# Clock_M-D.net
KiCad netlist of a schematic drawn in EAGLE
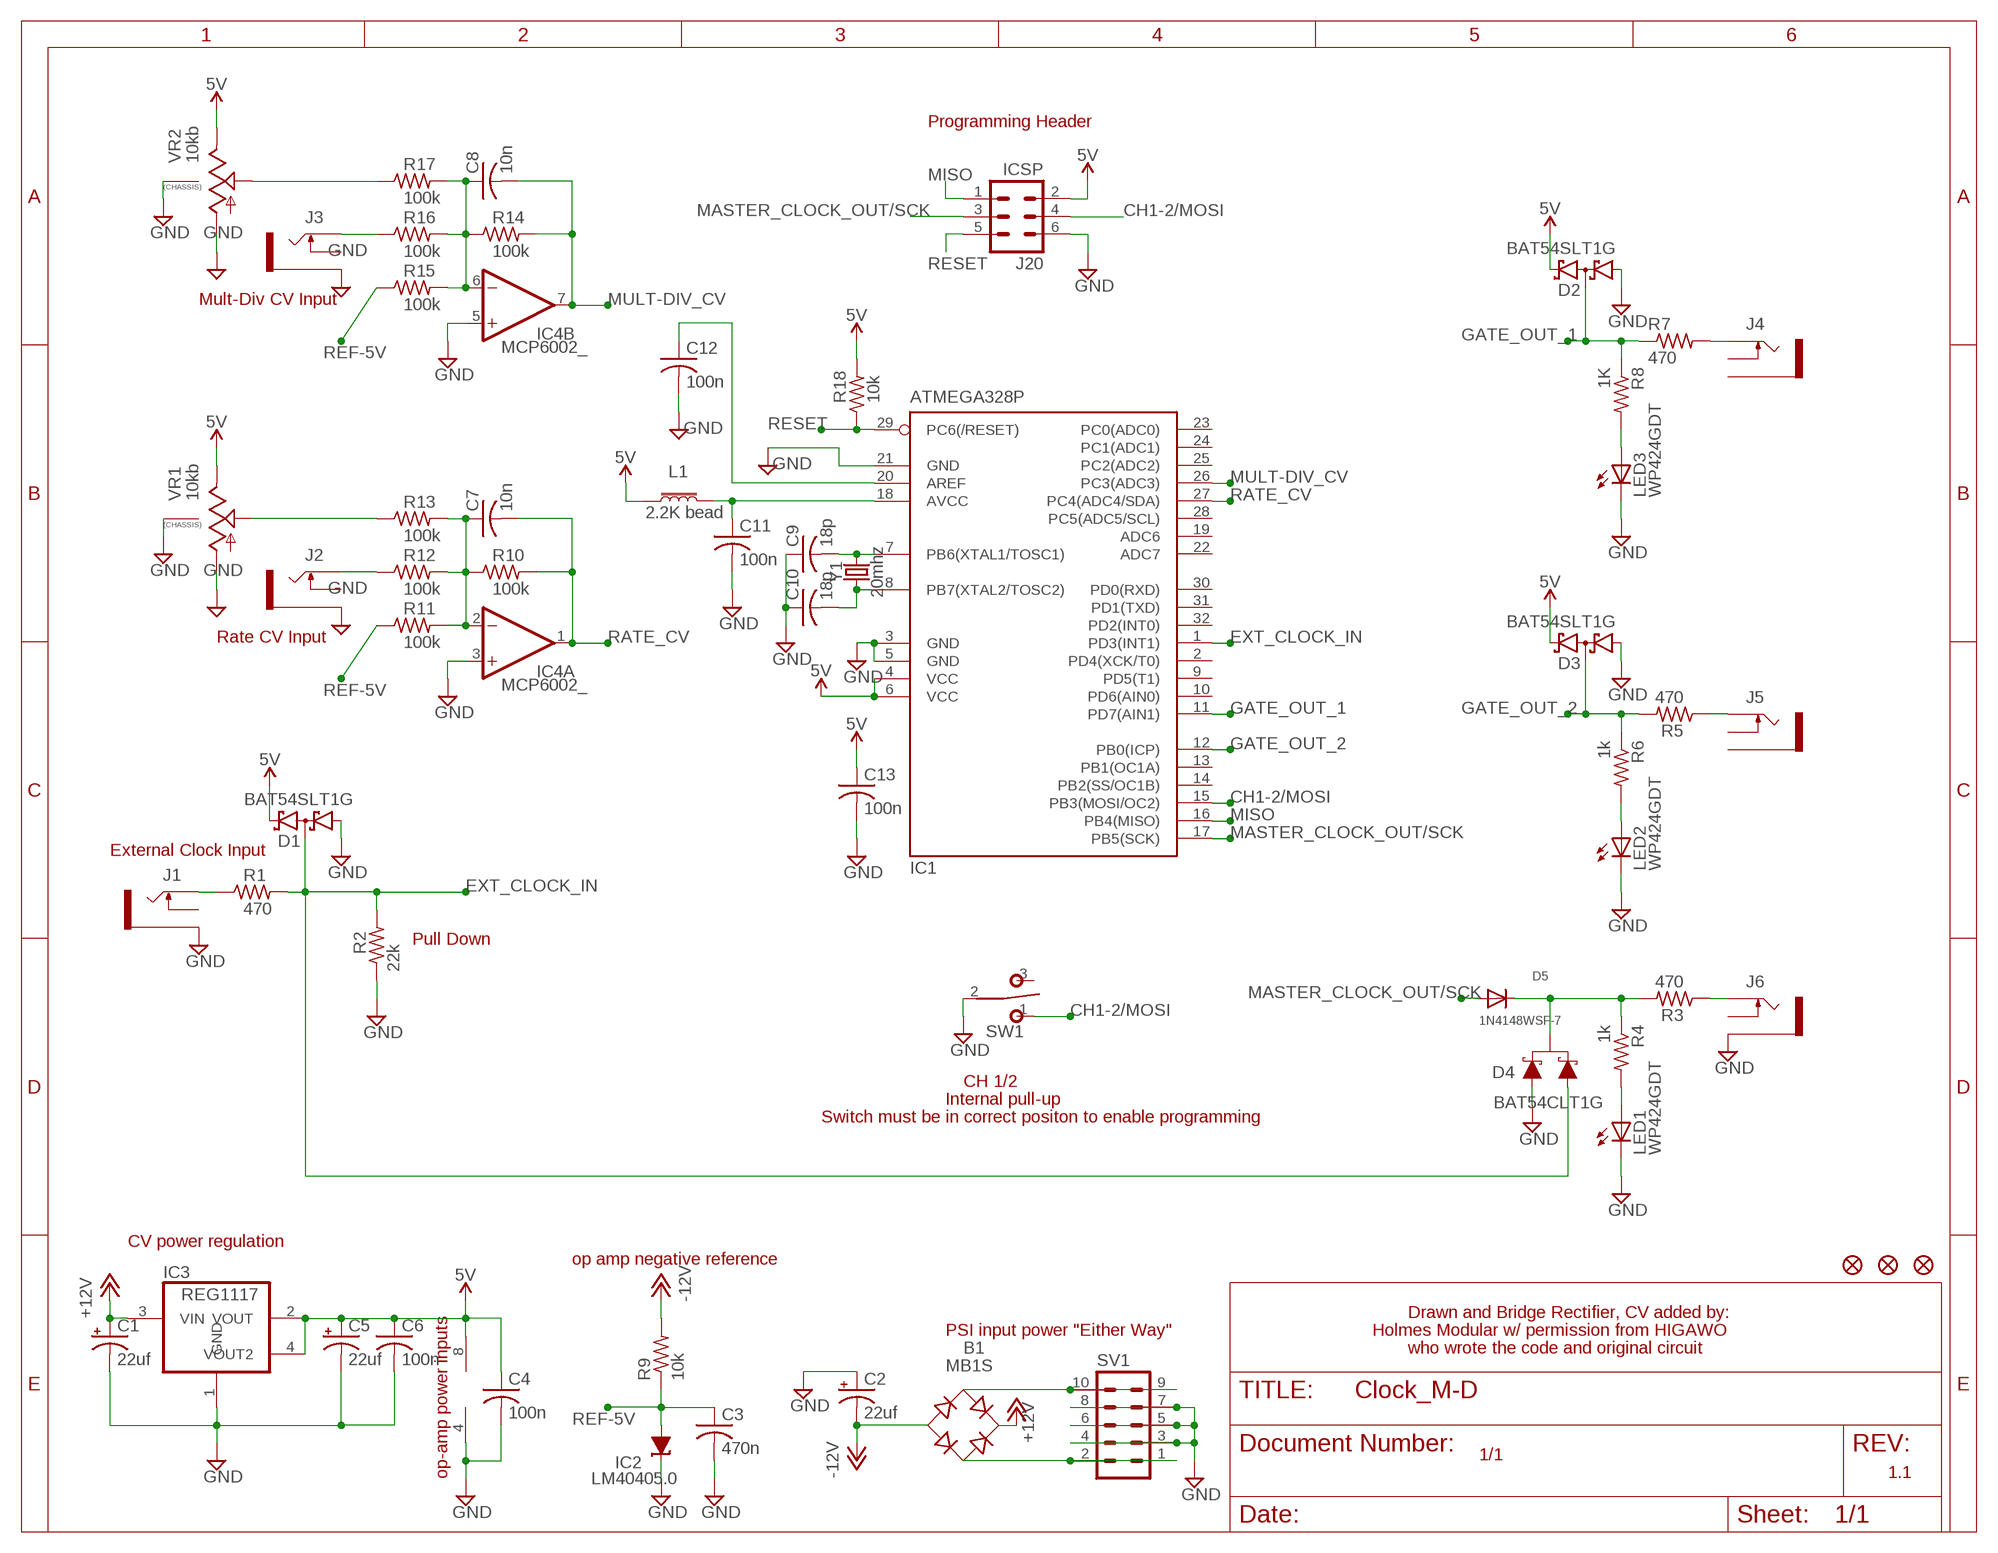
[diagram p0: schematic, sheet 1]

(export (version "E")
  (design (tool "Eeschema 10.0.6"))
  (components
    (comp (ref "B1")
      (value "MB1S")
      (footprint "eagle-import:SOIC-4")
      (libsource (lib "eagle-import") (part "MBS1"))
    )
    (comp (ref "C1")
      (value "22uf")
      (footprint "eagle-import:PANASONIC_C")
      (libsource (lib "eagle-import") (part "CPOL-USC"))
    )
    (comp (ref "C2")
      (value "22uf")
      (footprint "eagle-import:PANASONIC_C")
      (libsource (lib "eagle-import") (part "CPOL-USC"))
    )
    (comp (ref "C3")
      (value "470n")
      (footprint "eagle-import:C0805K")
      (libsource (lib "eagle-import") (part "C-USC0805K"))
    )
    (comp (ref "C4")
      (value "100n")
      (footprint "eagle-import:C0805K")
      (libsource (lib "eagle-import") (part "C-USC0805K"))
    )
    (comp (ref "C5")
      (value "22uf")
      (footprint "eagle-import:PANASONIC_C")
      (libsource (lib "eagle-import") (part "CPOL-USC"))
    )
    (comp (ref "C6")
      (value "100n")
      (footprint "eagle-import:C0805K")
      (libsource (lib "eagle-import") (part "C-USC0805K"))
    )
    (comp (ref "C7")
      (value "10n")
      (footprint "eagle-import:C0805K")
      (libsource (lib "eagle-import") (part "C-USC0805K"))
    )
    (comp (ref "C8")
      (value "10n")
      (footprint "eagle-import:C0805K")
      (libsource (lib "eagle-import") (part "C-USC0805K"))
    )
    (comp (ref "C9")
      (value "18p")
      (footprint "eagle-import:C0805K")
      (libsource (lib "eagle-import") (part "C-USC0805K"))
    )
    (comp (ref "C10")
      (value "18p")
      (footprint "eagle-import:C0805K")
      (libsource (lib "eagle-import") (part "C-USC0805K"))
    )
    (comp (ref "C11")
      (value "100n")
      (footprint "eagle-import:C0805K")
      (libsource (lib "eagle-import") (part "C-USC0805K"))
    )
    (comp (ref "C12")
      (value "100n")
      (footprint "eagle-import:C0805K")
      (libsource (lib "eagle-import") (part "C-USC0805K"))
    )
    (comp (ref "C13")
      (value "100n")
      (footprint "eagle-import:C0805K")
      (libsource (lib "eagle-import") (part "C-USC0805K"))
    )
    (comp (ref "D1")
      (value "BAT54SLT1G")
      (footprint "eagle-import:SOT23")
      (libsource (lib "eagle-import") (part "BAS40-04"))
    )
    (comp (ref "D2")
      (value "BAT54SLT1G")
      (footprint "eagle-import:SOT23")
      (libsource (lib "eagle-import") (part "BAS40-04"))
    )
    (comp (ref "D3")
      (value "BAT54SLT1G")
      (footprint "eagle-import:SOT23")
      (libsource (lib "eagle-import") (part "BAS40-04"))
    )
    (comp (ref "D4")
      (value "BAT54CLT1G")
      (footprint "eagle-import:SOT23-3")
      (libsource (lib "eagle-import") (part "DIODE-SCHOTTKY-DUAL"))
    )
    (comp (ref "D5")
      (value "1N4148WSF-7")
      (footprint "eagle-import:SOD-323F")
      (libsource (lib "eagle-import") (part "DIODESOD-323F"))
    )
    (comp (ref "FD1")
      (value "FIDUCIAL1X2")
      (footprint "eagle-import:FIDUCIAL-1X2")
      (libsource (lib "eagle-import") (part "FIDUCIAL1X2"))
    )
    (comp (ref "FD2")
      (value "FIDUCIAL1X2")
      (footprint "eagle-import:FIDUCIAL-1X2")
      (libsource (lib "eagle-import") (part "FIDUCIAL1X2"))
    )
    (comp (ref "FD3")
      (value "FIDUCIAL1X2")
      (footprint "eagle-import:FIDUCIAL-1X2")
      (libsource (lib "eagle-import") (part "FIDUCIAL1X2"))
    )
    (comp (ref "IC1")
      (value "ATMEGA328P")
      (footprint "eagle-import:TQFP32-08")
      (fields (field (name "MPN") "ATMEGA8-16AU"))
      (libsource (lib "eagle-import") (part "MEGA8-AI"))
    )
    (comp (ref "IC2")
      (value "LM40405.0")
      (footprint "eagle-import:DBZ_R-PDSO-G3")
      (fields (field (name "MPN") "LM4041A12IDBZR"))
      (libsource (lib "eagle-import") (part "LM4041DBZA12"))
    )
    (comp (ref "IC3")
      (value "REG1117")
      (footprint "eagle-import:SOT223")
      (libsource (lib "eagle-import") (part "REG1117"))
    )
    (comp (ref "IC4")
      (value "MCP6002_")
      (footprint "eagle-import:SO08")
      (libsource (lib "eagle-import") (part "MCP6002_"))
    )
    (comp (ref "J1")
      (value "THONKICONNNEW")
      (footprint "eagle-import:WQP-PJ301M-12_JACK")
      (libsource (lib "eagle-import") (part "THONKICONNNEW"))
    )
    (comp (ref "J2")
      (value "THONKICONNNEW")
      (footprint "eagle-import:WQP-PJ301M-12_JACK")
      (libsource (lib "eagle-import") (part "THONKICONNNEW"))
    )
    (comp (ref "J3")
      (value "THONKICONNNEW")
      (footprint "eagle-import:WQP-PJ301M-12_JACK")
      (libsource (lib "eagle-import") (part "THONKICONNNEW"))
    )
    (comp (ref "J4")
      (value "THONKICONNNEW")
      (footprint "eagle-import:WQP-PJ301M-12_JACK")
      (libsource (lib "eagle-import") (part "THONKICONNNEW"))
    )
    (comp (ref "J5")
      (value "THONKICONNNEW")
      (footprint "eagle-import:WQP-PJ301M-12_JACK")
      (libsource (lib "eagle-import") (part "THONKICONNNEW"))
    )
    (comp (ref "J6")
      (value "THONKICONNNEW")
      (footprint "eagle-import:WQP-PJ301M-12_JACK")
      (libsource (lib "eagle-import") (part "THONKICONNNEW"))
    )
    (comp (ref "J20")
      (value "ICSP")
      (footprint "eagle-import:MA03-2")
      (libsource (lib "eagle-import") (part "MA03-2"))
    )
    (comp (ref "L1")
      (value "2.2K bead")
      (footprint "eagle-import:0603")
      (libsource (lib "eagle-import") (part "FERRITE_BEAD-0603"))
    )
    (comp (ref "LED1")
      (value "WP424GDT")
      (footprint "eagle-import:LED3MM")
      (libsource (lib "eagle-import") (part "LED3MM"))
    )
    (comp (ref "LED2")
      (value "WP424GDT")
      (footprint "eagle-import:LED3MM")
      (libsource (lib "eagle-import") (part "LED3MM"))
    )
    (comp (ref "LED3")
      (value "WP424GDT")
      (footprint "eagle-import:LED3MM")
      (libsource (lib "eagle-import") (part "LED3MM"))
    )
    (comp (ref "R1")
      (value "470")
      (footprint "eagle-import:R0805")
      (libsource (lib "eagle-import") (part "R-US_R0805"))
    )
    (comp (ref "R2")
      (value "22k")
      (footprint "eagle-import:R0805")
      (libsource (lib "eagle-import") (part "R-US_R0805"))
    )
    (comp (ref "R3")
      (value "470")
      (footprint "eagle-import:R0805")
      (libsource (lib "eagle-import") (part "R-US_R0805"))
    )
    (comp (ref "R4")
      (value "1k")
      (footprint "eagle-import:R0805")
      (libsource (lib "eagle-import") (part "R-US_R0805"))
    )
    (comp (ref "R5")
      (value "470")
      (footprint "eagle-import:R0805")
      (libsource (lib "eagle-import") (part "R-US_R0805"))
    )
    (comp (ref "R6")
      (value "1k")
      (footprint "eagle-import:R0805")
      (libsource (lib "eagle-import") (part "R-US_R0805"))
    )
    (comp (ref "R7")
      (value "470")
      (footprint "eagle-import:R0805")
      (libsource (lib "eagle-import") (part "R-US_R0805"))
    )
    (comp (ref "R8")
      (value "1K")
      (footprint "eagle-import:R0805")
      (libsource (lib "eagle-import") (part "R-US_R0805"))
    )
    (comp (ref "R9")
      (value "10k")
      (footprint "eagle-import:R0805")
      (libsource (lib "eagle-import") (part "R-US_R0805"))
    )
    (comp (ref "R10")
      (value "100k")
      (footprint "eagle-import:R0805")
      (libsource (lib "eagle-import") (part "R-US_R0805"))
    )
    (comp (ref "R11")
      (value "100k")
      (footprint "eagle-import:R0805")
      (libsource (lib "eagle-import") (part "R-US_R0805"))
    )
    (comp (ref "R12")
      (value "100k")
      (footprint "eagle-import:R0805")
      (libsource (lib "eagle-import") (part "R-US_R0805"))
    )
    (comp (ref "R13")
      (value "100k")
      (footprint "eagle-import:R0805")
      (libsource (lib "eagle-import") (part "R-US_R0805"))
    )
    (comp (ref "R14")
      (value "100k")
      (footprint "eagle-import:R0805")
      (libsource (lib "eagle-import") (part "R-US_R0805"))
    )
    (comp (ref "R15")
      (value "100k")
      (footprint "eagle-import:R0805")
      (libsource (lib "eagle-import") (part "R-US_R0805"))
    )
    (comp (ref "R16")
      (value "100k")
      (footprint "eagle-import:R0805")
      (libsource (lib "eagle-import") (part "R-US_R0805"))
    )
    (comp (ref "R17")
      (value "100k")
      (footprint "eagle-import:R0805")
      (libsource (lib "eagle-import") (part "R-US_R0805"))
    )
    (comp (ref "R18")
      (value "10k")
      (footprint "eagle-import:R0805")
      (libsource (lib "eagle-import") (part "R-US_R0805"))
    )
    (comp (ref "SV1")
      (value "EURO_POWER_HEADERLOCK")
      (footprint "eagle-import:10PIN_BACKSIDE")
      (libsource (lib "eagle-import") (part "10PIN_BACKSIDE"))
    )
    (comp (ref "SW1")
      (value "T-80-T-SPDT-ON-OFF-ON")
      (footprint "eagle-import:M9040P")
      (libsource (lib "eagle-import") (part "T-80-T-SPDT-ON-OFF-ON"))
    )
    (comp (ref "VR1")
      (value "10kb")
      (footprint "eagle-import:9MM_SNAP-IN_POT")
      (libsource (lib "eagle-import") (part "9MM_SNAP-IN_POT_CHASSIS"))
    )
    (comp (ref "VR2")
      (value "10kb")
      (footprint "eagle-import:9MM_SNAP-IN_POT")
      (libsource (lib "eagle-import") (part "9MM_SNAP-IN_POT_CHASSIS"))
    )
    (comp (ref "Y1")
      (value "20mhz")
      (footprint "eagle-import:CRYSTAL-SMD-5X3.2-2PAD")
      (libsource (lib "eagle-import") (part "CRYSTALSMD-5X3.2-2PAD"))
    )
  )
  (nets
    (net (code "1") (name "+12V") (class "Default")
      (node (ref "B1") (pin "+") (pinfunction "+_+") (pintype "passive"))
      (node (ref "C1") (pin "+") (pinfunction "+_+") (pintype "passive"))
      (node (ref "IC3") (pin "3") (pinfunction "VIN_3") (pintype "input"))
    )
    (net (code "2") (name "-12V") (class "Default")
      (node (ref "B1") (pin "-") (pinfunction "-_-") (pintype "passive"))
      (node (ref "C2") (pin "-") (pinfunction "-_-") (pintype "passive"))
      (node (ref "R9") (pin "2") (pinfunction "2_2") (pintype "passive"))
    )
    (net (code "3") (name "/CH1-2{slash}MOSI") (class "Default")
      (node (ref "IC1") (pin "15") (pinfunction "PB3(MOSI/OC2)_15") (pintype "bidirectional"))
      (node (ref "J20") (pin "4") (pinfunction "4_4") (pintype "passive"))
      (node (ref "SW1") (pin "1") (pinfunction "O_1") (pintype "passive"))
    )
    (net (code "4") (name "/EXT_CLOCK_IN") (class "Default")
      (node (ref "D1") (pin "3") (pinfunction "C1A2_3") (pintype "passive"))
      (node (ref "D4") (pin "2") (pinfunction "A1_2") (pintype "passive"))
      (node (ref "IC1") (pin "1") (pinfunction "PD3(INT1)_1") (pintype "bidirectional"))
      (node (ref "R1") (pin "2") (pinfunction "2_2") (pintype "passive"))
      (node (ref "R2") (pin "2") (pinfunction "2_2") (pintype "passive"))
    )
    (net (code "5") (name "/GATE_OUT_1") (class "Default")
      (node (ref "D2") (pin "3") (pinfunction "C1A2_3") (pintype "passive"))
      (node (ref "IC1") (pin "11") (pinfunction "PD7(AIN1)_11") (pintype "bidirectional"))
      (node (ref "R7") (pin "1") (pinfunction "1_1") (pintype "passive"))
      (node (ref "R8") (pin "1") (pinfunction "1_1") (pintype "passive"))
    )
    (net (code "6") (name "/GATE_OUT_2") (class "Default")
      (node (ref "D3") (pin "3") (pinfunction "C1A2_3") (pintype "passive"))
      (node (ref "IC1") (pin "12") (pinfunction "PB0(ICP)_12") (pintype "bidirectional"))
      (node (ref "R5") (pin "2") (pinfunction "2_2") (pintype "passive"))
      (node (ref "R6") (pin "1") (pinfunction "1_1") (pintype "passive"))
    )
    (net (code "7") (name "/MASTER_CLOCK_OUT{slash}SCK") (class "Default")
      (node (ref "D5") (pin "A") (pinfunction "A_A") (pintype "passive"))
      (node (ref "IC1") (pin "17") (pinfunction "PB5(SCK)_17") (pintype "bidirectional"))
      (node (ref "J20") (pin "3") (pinfunction "3_3") (pintype "passive"))
    )
    (net (code "8") (name "/MISO") (class "Default")
      (node (ref "IC1") (pin "16") (pinfunction "PB4(MISO)_16") (pintype "bidirectional"))
      (node (ref "J20") (pin "1") (pinfunction "1_1") (pintype "passive"))
    )
    (net (code "9") (name "/MULT-DIV_CV") (class "Default")
      (node (ref "C8") (pin "2") (pinfunction "2_2") (pintype "passive"))
      (node (ref "IC1") (pin "26") (pinfunction "PC3(ADC3)_26") (pintype "bidirectional"))
      (node (ref "IC4") (pin "7") (pinfunction "OUT_7") (pintype "output"))
      (node (ref "R14") (pin "2") (pinfunction "2_2") (pintype "passive"))
    )
    (net (code "10") (name "/RATE_CV") (class "Default")
      (node (ref "C7") (pin "2") (pinfunction "2_2") (pintype "passive"))
      (node (ref "IC1") (pin "27") (pinfunction "PC4(ADC4/SDA)_27") (pintype "bidirectional"))
      (node (ref "IC4") (pin "1") (pinfunction "OUT_1") (pintype "output"))
      (node (ref "R10") (pin "2") (pinfunction "2_2") (pintype "passive"))
    )
    (net (code "11") (name "/REF-5V") (class "Default")
      (node (ref "C3") (pin "1") (pinfunction "1_1") (pintype "passive"))
      (node (ref "IC2") (pin "2") (pinfunction "A_2") (pintype "passive"))
      (node (ref "R11") (pin "1") (pinfunction "1_1") (pintype "passive"))
      (node (ref "R15") (pin "1") (pinfunction "1_1") (pintype "passive"))
      (node (ref "R9") (pin "1") (pinfunction "1_1") (pintype "passive"))
    )
    (net (code "12") (name "/RESET") (class "Default")
      (node (ref "IC1") (pin "29") (pinfunction "PC6(/RESET)_29") (pintype "bidirectional"))
      (node (ref "J20") (pin "5") (pinfunction "5_5") (pintype "passive"))
      (node (ref "R18") (pin "1") (pinfunction "1_1") (pintype "passive"))
    )
    (net (code "13") (name "5V") (class "Default")
      (node (ref "C13") (pin "1") (pinfunction "1_1") (pintype "passive"))
      (node (ref "C4") (pin "1") (pinfunction "1_1") (pintype "passive"))
      (node (ref "C5") (pin "+") (pinfunction "+_+") (pintype "passive"))
      (node (ref "C6") (pin "1") (pinfunction "1_1") (pintype "passive"))
      (node (ref "D1") (pin "2") (pinfunction "C2_2") (pintype "passive"))
      (node (ref "D2") (pin "2") (pinfunction "C2_2") (pintype "passive"))
      (node (ref "D3") (pin "2") (pinfunction "C2_2") (pintype "passive"))
      (node (ref "IC1") (pin "4") (pinfunction "VCC_4") (pintype "power_in"))
      (node (ref "IC1") (pin "6") (pinfunction "VCC_6") (pintype "power_in"))
      (node (ref "IC3") (pin "2") (pinfunction "VOUT_2") (pintype "output"))
      (node (ref "IC3") (pin "4") (pinfunction "VOUT2_4") (pintype "output"))
      (node (ref "IC4") (pin "8") (pinfunction "V+_8") (pintype "power_in"))
      (node (ref "J20") (pin "2") (pinfunction "2_2") (pintype "passive"))
      (node (ref "L1") (pin "1") (pinfunction "1_1") (pintype "passive"))
      (node (ref "R18") (pin "2") (pinfunction "2_2") (pintype "passive"))
      (node (ref "VR1") (pin "3") (pinfunction "E_3") (pintype "passive"))
      (node (ref "VR2") (pin "3") (pinfunction "E_3") (pintype "passive"))
    )
    (net (code "14") (name "GND") (class "Default")
      (node (ref "C1") (pin "-") (pinfunction "-_-") (pintype "passive"))
      (node (ref "C10") (pin "1") (pinfunction "1_1") (pintype "passive"))
      (node (ref "C11") (pin "2") (pinfunction "2_2") (pintype "passive"))
      (node (ref "C12") (pin "2") (pinfunction "2_2") (pintype "passive"))
      (node (ref "C13") (pin "2") (pinfunction "2_2") (pintype "passive"))
      (node (ref "C2") (pin "+") (pinfunction "+_+") (pintype "passive"))
      (node (ref "C3") (pin "2") (pinfunction "2_2") (pintype "passive"))
      (node (ref "C4") (pin "2") (pinfunction "2_2") (pintype "passive"))
      (node (ref "C5") (pin "-") (pinfunction "-_-") (pintype "passive"))
      (node (ref "C6") (pin "2") (pinfunction "2_2") (pintype "passive"))
      (node (ref "C9") (pin "1") (pinfunction "1_1") (pintype "passive"))
      (node (ref "D1") (pin "1") (pinfunction "A1_1") (pintype "passive"))
      (node (ref "D2") (pin "1") (pinfunction "A1_1") (pintype "passive"))
      (node (ref "D3") (pin "1") (pinfunction "A1_1") (pintype "passive"))
      (node (ref "D4") (pin "1") (pinfunction "A_1") (pintype "passive"))
      (node (ref "IC1") (pin "21") (pinfunction "GND_21") (pintype "power_in"))
      (node (ref "IC1") (pin "3") (pinfunction "GND_3") (pintype "power_in"))
      (node (ref "IC1") (pin "5") (pinfunction "GND_5") (pintype "power_in"))
      (node (ref "IC2") (pin "1") (pinfunction "C_1") (pintype "passive"))
      (node (ref "IC3") (pin "1") (pinfunction "GND_1") (pintype "power_in"))
      (node (ref "IC4") (pin "3") (pinfunction "+IN_3") (pintype "input"))
      (node (ref "IC4") (pin "4") (pinfunction "V-_4") (pintype "power_in"))
      (node (ref "IC4") (pin "5") (pinfunction "+IN_5") (pintype "input"))
      (node (ref "J1") (pin "P$3_SLEEVE") (pinfunction "SLEEVE_P$3_SLEEVE") (pintype "passive"))
      (node (ref "J2") (pin "P$3_SLEEVE") (pinfunction "SLEEVE_P$3_SLEEVE") (pintype "passive"))
      (node (ref "J20") (pin "6") (pinfunction "6_6") (pintype "passive"))
      (node (ref "J3") (pin "P$3_SLEEVE") (pinfunction "SLEEVE_P$3_SLEEVE") (pintype "passive"))
      (node (ref "J6") (pin "P$3_SLEEVE") (pinfunction "SLEEVE_P$3_SLEEVE") (pintype "passive"))
      (node (ref "LED1") (pin "K") (pinfunction "C_K") (pintype "passive"))
      (node (ref "LED2") (pin "K") (pinfunction "C_K") (pintype "passive"))
      (node (ref "LED3") (pin "K") (pinfunction "C_K") (pintype "passive"))
      (node (ref "R2") (pin "1") (pinfunction "1_1") (pintype "passive"))
      (node (ref "SV1") (pin "3") (pinfunction "3_3") (pintype "passive"))
      (node (ref "SV1") (pin "4") (pinfunction "4_4") (pintype "passive"))
      (node (ref "SV1") (pin "5") (pinfunction "5_5") (pintype "passive"))
      (node (ref "SV1") (pin "6") (pinfunction "6_6") (pintype "passive"))
      (node (ref "SV1") (pin "7") (pinfunction "7_7") (pintype "passive"))
      (node (ref "SV1") (pin "8") (pinfunction "8_8") (pintype "passive"))
      (node (ref "SW1") (pin "2") (pinfunction "P_2") (pintype "passive"))
      (node (ref "VR1") (pin "1") (pinfunction "A_1") (pintype "passive"))
      (node (ref "VR1") (pin "CHASSIS1") (pinfunction "P$1_CHASSIS1") (pintype "passive"))
      (node (ref "VR1") (pin "CHASSIS2") (pinfunction "P$1_CHASSIS2") (pintype "passive"))
      (node (ref "VR2") (pin "1") (pinfunction "A_1") (pintype "passive"))
      (node (ref "VR2") (pin "CHASSIS1") (pinfunction "P$1_CHASSIS1") (pintype "passive"))
      (node (ref "VR2") (pin "CHASSIS2") (pinfunction "P$1_CHASSIS2") (pintype "passive"))
    )
    (net (code "15") (name "Net-(B1-AC1)") (class "Default")
      (node (ref "B1") (pin "~1") (pinfunction "AC1_~1") (pintype "passive"))
      (node (ref "SV1") (pin "10") (pinfunction "10_10") (pintype "passive"))
      (node (ref "SV1") (pin "9") (pinfunction "9_9") (pintype "passive"))
    )
    (net (code "16") (name "Net-(B1-AC2)") (class "Default")
      (node (ref "B1") (pin "~2") (pinfunction "AC2_~2") (pintype "passive"))
      (node (ref "SV1") (pin "1") (pinfunction "1_1") (pintype "passive"))
      (node (ref "SV1") (pin "2") (pinfunction "2_2") (pintype "passive"))
    )
    (net (code "17") (name "Net-(D4-C)") (class "Default")
      (node (ref "D4") (pin "3") (pinfunction "C_3") (pintype "passive"))
      (node (ref "D5") (pin "C") (pinfunction "C_C") (pintype "passive"))
      (node (ref "R3") (pin "2") (pinfunction "2_2") (pintype "passive"))
      (node (ref "R4") (pin "1") (pinfunction "1_1") (pintype "passive"))
    )
    (net (code "18") (name "Net-(IC1-AREF)") (class "Default")
      (node (ref "C12") (pin "1") (pinfunction "1_1") (pintype "passive"))
      (node (ref "IC1") (pin "20") (pinfunction "AREF_20") (pintype "passive"))
    )
    (net (code "19") (name "Net-(IC1-AVCC)") (class "Default")
      (node (ref "C11") (pin "1") (pinfunction "1_1") (pintype "passive"))
      (node (ref "IC1") (pin "18") (pinfunction "AVCC_18") (pintype "power_in"))
      (node (ref "L1") (pin "2") (pinfunction "2_2") (pintype "passive"))
    )
    (net (code "20") (name "Net-(IC1-PB6(XTAL1{slash}TOSC1))") (class "Default")
      (node (ref "C9") (pin "2") (pinfunction "2_2") (pintype "passive"))
      (node (ref "IC1") (pin "7") (pinfunction "PB6(XTAL1/TOSC1)_7") (pintype "bidirectional"))
      (node (ref "Y1") (pin "P$2") (pinfunction "2_P$2") (pintype "passive"))
    )
    (net (code "21") (name "Net-(IC1-PB7(XTAL2{slash}TOSC2))") (class "Default")
      (node (ref "C10") (pin "2") (pinfunction "2_2") (pintype "passive"))
      (node (ref "IC1") (pin "8") (pinfunction "PB7(XTAL2/TOSC2)_8") (pintype "bidirectional"))
      (node (ref "Y1") (pin "P$1") (pinfunction "1_P$1") (pintype "passive"))
    )
    (net (code "22") (name "Net-(IC4A--IN)") (class "Default")
      (node (ref "C7") (pin "1") (pinfunction "1_1") (pintype "passive"))
      (node (ref "IC4") (pin "2") (pinfunction "-IN_2") (pintype "input"))
      (node (ref "R10") (pin "1") (pinfunction "1_1") (pintype "passive"))
      (node (ref "R11") (pin "2") (pinfunction "2_2") (pintype "passive"))
      (node (ref "R12") (pin "2") (pinfunction "2_2") (pintype "passive"))
      (node (ref "R13") (pin "2") (pinfunction "2_2") (pintype "passive"))
    )
    (net (code "23") (name "Net-(IC4B--IN)") (class "Default")
      (node (ref "C8") (pin "1") (pinfunction "1_1") (pintype "passive"))
      (node (ref "IC4") (pin "6") (pinfunction "-IN_6") (pintype "input"))
      (node (ref "R14") (pin "1") (pinfunction "1_1") (pintype "passive"))
      (node (ref "R15") (pin "2") (pinfunction "2_2") (pintype "passive"))
      (node (ref "R16") (pin "2") (pinfunction "2_2") (pintype "passive"))
      (node (ref "R17") (pin "2") (pinfunction "2_2") (pintype "passive"))
    )
    (net (code "24") (name "Net-(J1-TIP)") (class "Default")
      (node (ref "J1") (pin "P$1_TIP") (pinfunction "TIP_P$1_TIP") (pintype "passive"))
      (node (ref "R1") (pin "1") (pinfunction "1_1") (pintype "passive"))
    )
    (net (code "25") (name "Net-(J2-TIP)") (class "Default")
      (node (ref "J2") (pin "P$1_TIP") (pinfunction "TIP_P$1_TIP") (pintype "passive"))
      (node (ref "R12") (pin "1") (pinfunction "1_1") (pintype "passive"))
    )
    (net (code "26") (name "Net-(J3-TIP)") (class "Default")
      (node (ref "J3") (pin "P$1_TIP") (pinfunction "TIP_P$1_TIP") (pintype "passive"))
      (node (ref "R16") (pin "1") (pinfunction "1_1") (pintype "passive"))
    )
    (net (code "27") (name "Net-(J4-TIP)") (class "Default")
      (node (ref "J4") (pin "P$1_TIP") (pinfunction "TIP_P$1_TIP") (pintype "passive"))
      (node (ref "R7") (pin "2") (pinfunction "2_2") (pintype "passive"))
    )
    (net (code "28") (name "Net-(J5-TIP)") (class "Default")
      (node (ref "J5") (pin "P$1_TIP") (pinfunction "TIP_P$1_TIP") (pintype "passive"))
      (node (ref "R5") (pin "1") (pinfunction "1_1") (pintype "passive"))
    )
    (net (code "29") (name "Net-(J6-TIP)") (class "Default")
      (node (ref "J6") (pin "P$1_TIP") (pinfunction "TIP_P$1_TIP") (pintype "passive"))
      (node (ref "R3") (pin "1") (pinfunction "1_1") (pintype "passive"))
    )
    (net (code "30") (name "Net-(LED1-PadA)") (class "Default")
      (node (ref "LED1") (pin "A") (pinfunction "A_A") (pintype "passive"))
      (node (ref "R4") (pin "2") (pinfunction "2_2") (pintype "passive"))
    )
    (net (code "31") (name "Net-(LED2-PadA)") (class "Default")
      (node (ref "LED2") (pin "A") (pinfunction "A_A") (pintype "passive"))
      (node (ref "R6") (pin "2") (pinfunction "2_2") (pintype "passive"))
    )
    (net (code "32") (name "Net-(LED3-PadA)") (class "Default")
      (node (ref "LED3") (pin "A") (pinfunction "A_A") (pintype "passive"))
      (node (ref "R8") (pin "2") (pinfunction "2_2") (pintype "passive"))
    )
    (net (code "33") (name "Net-(VR1-S)") (class "Default")
      (node (ref "R13") (pin "1") (pinfunction "1_1") (pintype "passive"))
      (node (ref "VR1") (pin "2") (pinfunction "S_2") (pintype "passive"))
    )
    (net (code "34") (name "Net-(VR2-S)") (class "Default")
      (node (ref "R17") (pin "1") (pinfunction "1_1") (pintype "passive"))
      (node (ref "VR2") (pin "2") (pinfunction "S_2") (pintype "passive"))
    )
    (net (code "35") (name "unconnected-(IC1-ADC6-Pad19)") (class "Default")
      (node (ref "IC1") (pin "19") (pinfunction "ADC6_19") (pintype "bidirectional"))
    )
    (net (code "36") (name "unconnected-(IC1-ADC7-Pad22)") (class "Default")
      (node (ref "IC1") (pin "22") (pinfunction "ADC7_22") (pintype "bidirectional"))
    )
    (net (code "37") (name "unconnected-(IC1-PB1(OC1A)-Pad13)") (class "Default")
      (node (ref "IC1") (pin "13") (pinfunction "PB1(OC1A)_13") (pintype "bidirectional"))
    )
    (net (code "38") (name "unconnected-(IC1-PB2(SS{slash}OC1B)-Pad14)") (class "Default")
      (node (ref "IC1") (pin "14") (pinfunction "PB2(SS/OC1B)_14") (pintype "bidirectional"))
    )
    (net (code "39") (name "unconnected-(IC1-PC0(ADC0)-Pad23)") (class "Default")
      (node (ref "IC1") (pin "23") (pinfunction "PC0(ADC0)_23") (pintype "bidirectional"))
    )
    (net (code "40") (name "unconnected-(IC1-PC1(ADC1)-Pad24)") (class "Default")
      (node (ref "IC1") (pin "24") (pinfunction "PC1(ADC1)_24") (pintype "bidirectional"))
    )
    (net (code "41") (name "unconnected-(IC1-PC2(ADC2)-Pad25)") (class "Default")
      (node (ref "IC1") (pin "25") (pinfunction "PC2(ADC2)_25") (pintype "bidirectional"))
    )
    (net (code "42") (name "unconnected-(IC1-PC5(ADC5{slash}SCL)-Pad28)") (class "Default")
      (node (ref "IC1") (pin "28") (pinfunction "PC5(ADC5/SCL)_28") (pintype "bidirectional"))
    )
    (net (code "43") (name "unconnected-(IC1-PD0(RXD)-Pad30)") (class "Default")
      (node (ref "IC1") (pin "30") (pinfunction "PD0(RXD)_30") (pintype "bidirectional"))
    )
    (net (code "44") (name "unconnected-(IC1-PD1(TXD)-Pad31)") (class "Default")
      (node (ref "IC1") (pin "31") (pinfunction "PD1(TXD)_31") (pintype "bidirectional"))
    )
    (net (code "45") (name "unconnected-(IC1-PD2(INT0)-Pad32)") (class "Default")
      (node (ref "IC1") (pin "32") (pinfunction "PD2(INT0)_32") (pintype "bidirectional"))
    )
    (net (code "46") (name "unconnected-(IC1-PD4(XCK{slash}T0)-Pad2)") (class "Default")
      (node (ref "IC1") (pin "2") (pinfunction "PD4(XCK/T0)_2") (pintype "bidirectional"))
    )
    (net (code "47") (name "unconnected-(IC1-PD5(T1)-Pad9)") (class "Default")
      (node (ref "IC1") (pin "9") (pinfunction "PD5(T1)_9") (pintype "bidirectional"))
    )
    (net (code "48") (name "unconnected-(IC1-PD6(AIN0)-Pad10)") (class "Default")
      (node (ref "IC1") (pin "10") (pinfunction "PD6(AIN0)_10") (pintype "bidirectional"))
    )
    (net (code "49") (name "unconnected-(J1-SWITCH-PadP$2_SWITCH)") (class "Default")
      (node (ref "J1") (pin "P$2_SWITCH") (pinfunction "SWITCH_P$2_SWITCH") (pintype "passive"))
    )
    (net (code "50") (name "unconnected-(J2-SWITCH-PadP$2_SWITCH)") (class "Default")
      (node (ref "J2") (pin "P$2_SWITCH") (pinfunction "SWITCH_P$2_SWITCH") (pintype "passive"))
    )
    (net (code "51") (name "unconnected-(J3-SWITCH-PadP$2_SWITCH)") (class "Default")
      (node (ref "J3") (pin "P$2_SWITCH") (pinfunction "SWITCH_P$2_SWITCH") (pintype "passive"))
    )
    (net (code "52") (name "unconnected-(J4-SLEEVE-PadP$3_SLEEVE)") (class "Default")
      (node (ref "J4") (pin "P$3_SLEEVE") (pinfunction "SLEEVE_P$3_SLEEVE") (pintype "passive"))
    )
    (net (code "53") (name "unconnected-(J4-SWITCH-PadP$2_SWITCH)") (class "Default")
      (node (ref "J4") (pin "P$2_SWITCH") (pinfunction "SWITCH_P$2_SWITCH") (pintype "passive"))
    )
    (net (code "54") (name "unconnected-(J5-SLEEVE-PadP$3_SLEEVE)") (class "Default")
      (node (ref "J5") (pin "P$3_SLEEVE") (pinfunction "SLEEVE_P$3_SLEEVE") (pintype "passive"))
    )
    (net (code "55") (name "unconnected-(J5-SWITCH-PadP$2_SWITCH)") (class "Default")
      (node (ref "J5") (pin "P$2_SWITCH") (pinfunction "SWITCH_P$2_SWITCH") (pintype "passive"))
    )
    (net (code "56") (name "unconnected-(J6-SWITCH-PadP$2_SWITCH)") (class "Default")
      (node (ref "J6") (pin "P$2_SWITCH") (pinfunction "SWITCH_P$2_SWITCH") (pintype "passive"))
    )
    (net (code "57") (name "unconnected-(SW1-S-Pad3)") (class "Default")
      (node (ref "SW1") (pin "3") (pinfunction "S_3") (pintype "passive"))
    )
  )
)
